# DIY-Cellphone.net
KiCad netlist of a schematic drawn in EAGLE
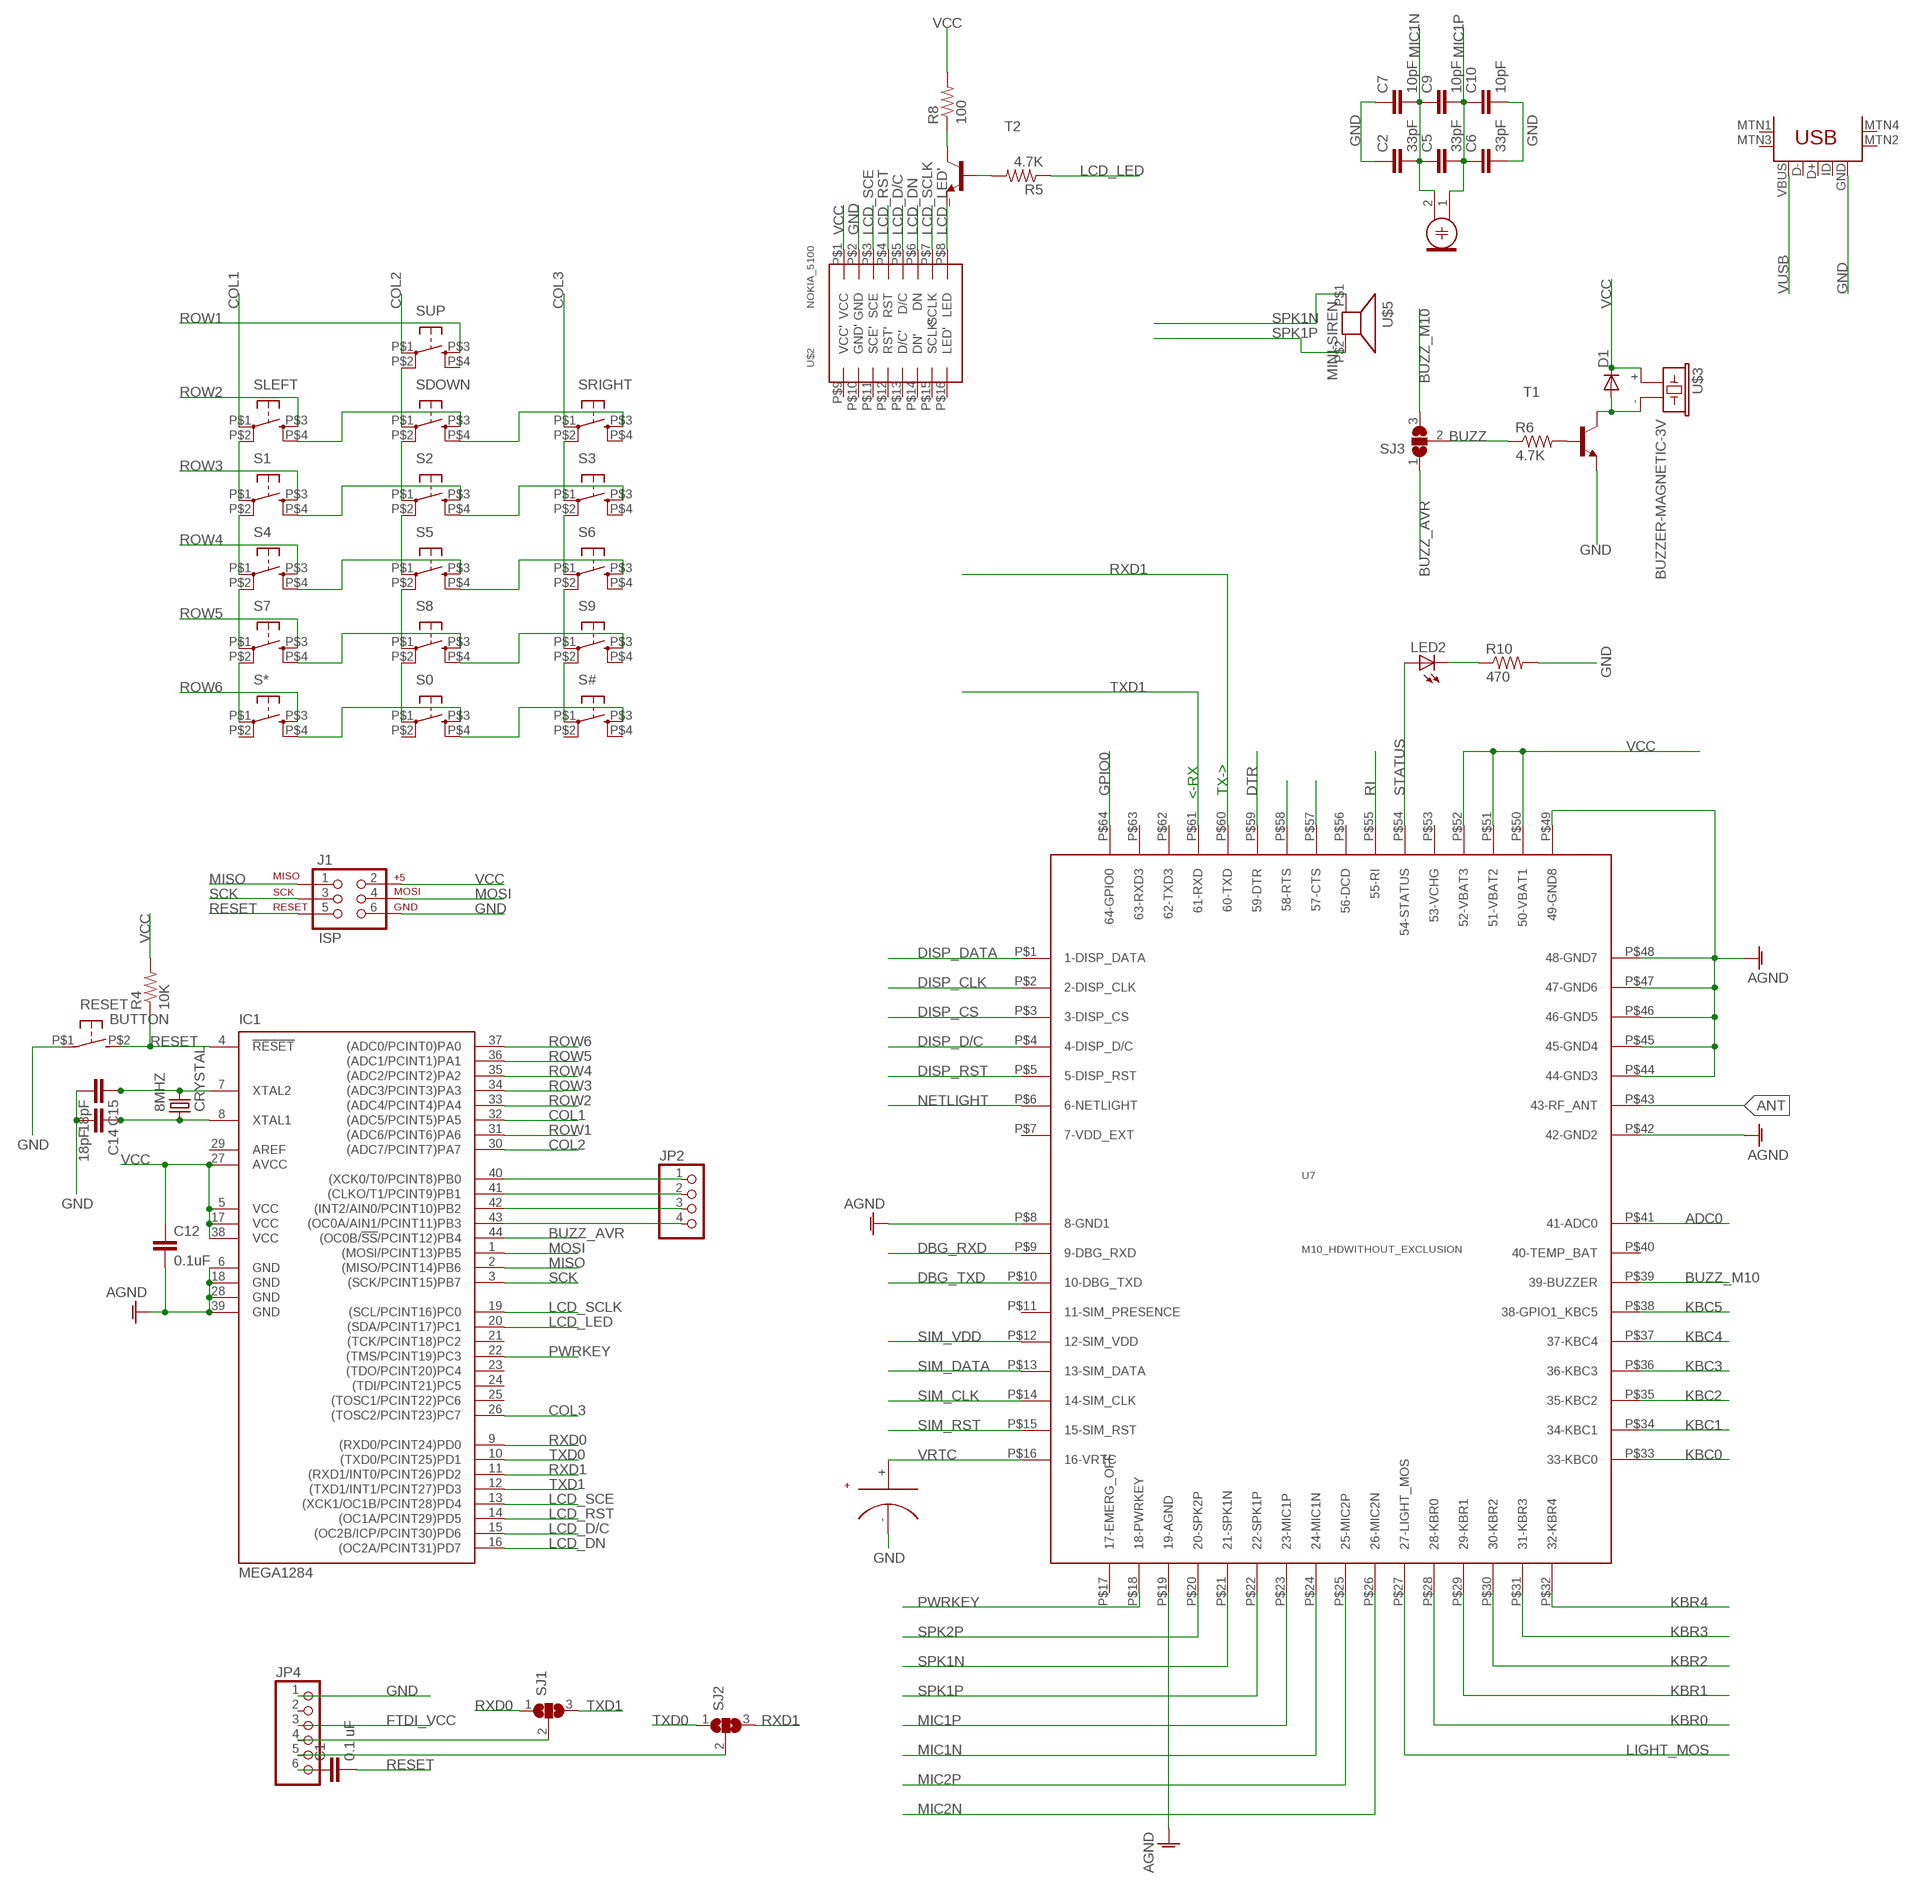
[diagram p0: schematic, sheet 1, part 1 of 2]
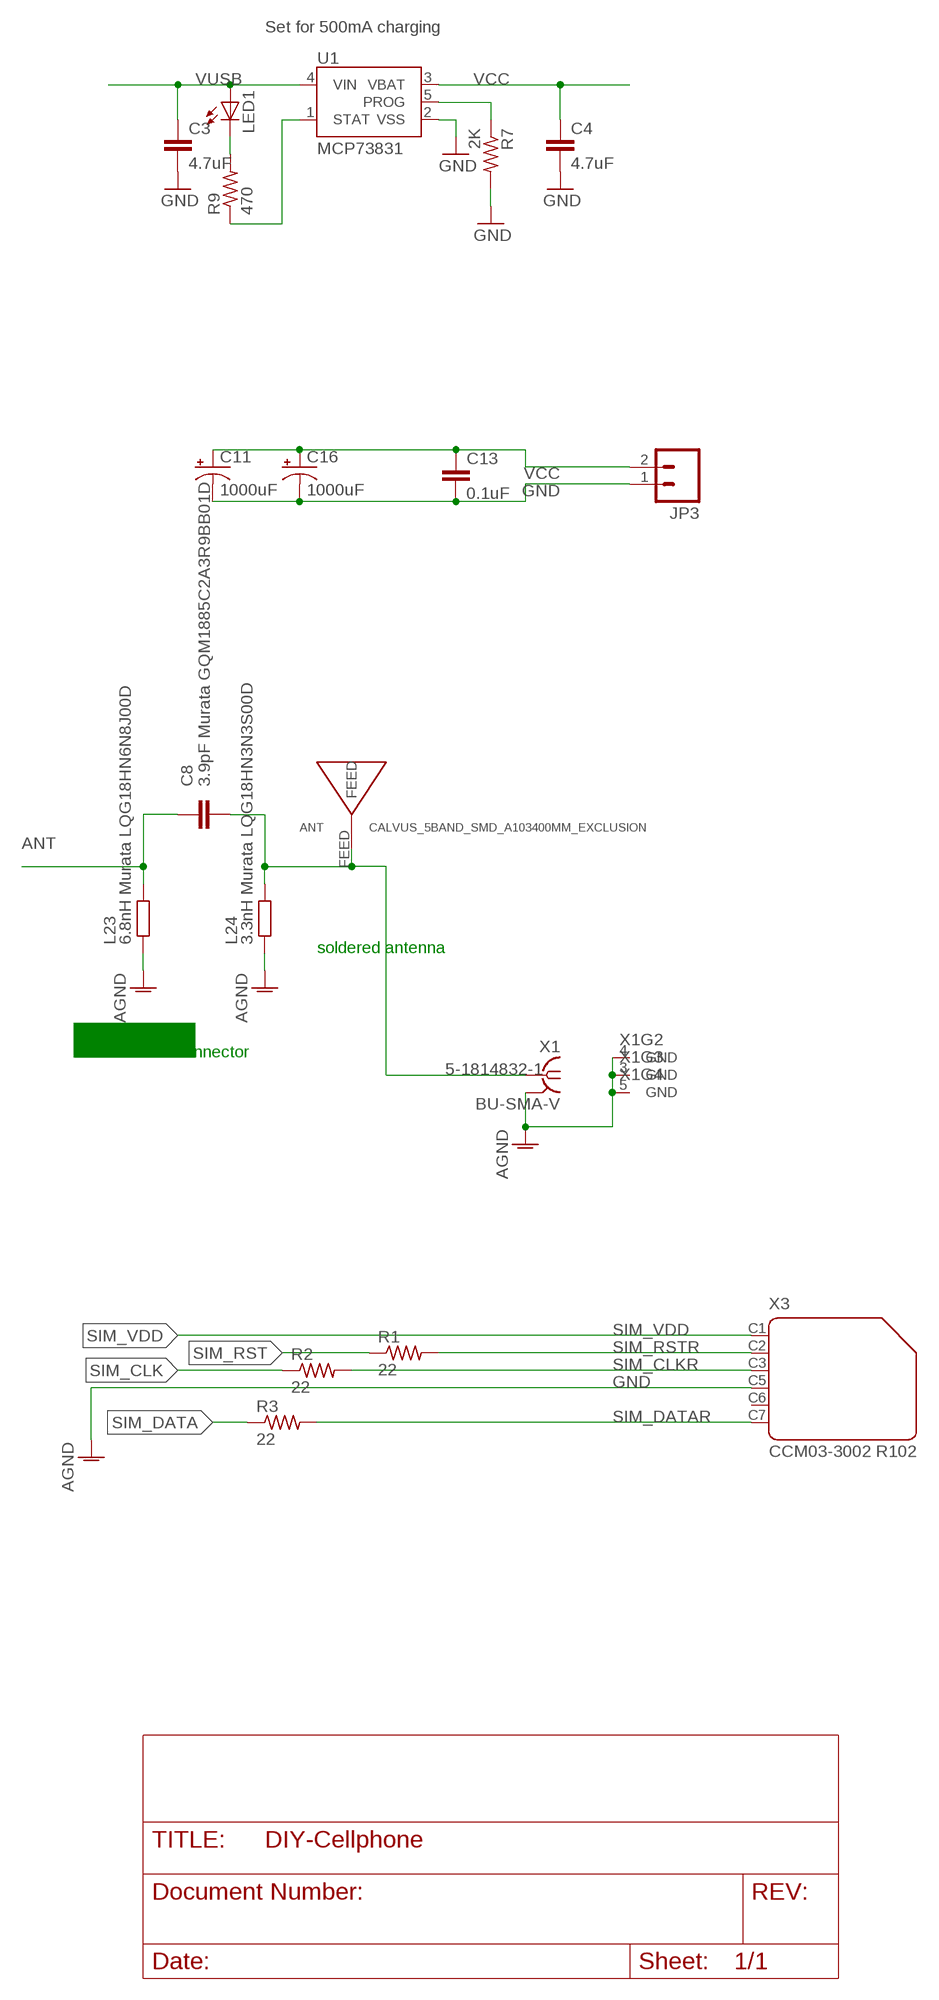
[diagram p1: schematic, sheet 1, part 2 of 2]

(export (version "E")
  (design (tool "Eeschema 10.0.6"))
  (components
    (comp (ref "8MHZ")
      (value "CRYSTAL")
      (footprint "eagle-import:2-SMD-5X3MM")
      (libsource (lib "eagle-import") (part "CRYSTAL"))
    )
    (comp (ref "ANT")
      (value "CALVUS_5BAND_SMD_A103400MM_EXCLUSION")
      (footprint "eagle-import:CALVUS_5BAND_SMD_A10340_0MM_EXCLUSION")
      (libsource (lib "eagle-import") (part "CALVUS_5BAND_SMD_A103400MM_EXCLUSION"))
    )
    (comp (ref "C1")
      (value "0.1 uF")
      (footprint "eagle-import:C1206")
      (libsource (lib "eagle-import") (part "cellphone-rcl_C-EUC1206"))
    )
    (comp (ref "C2")
      (value "33pF")
      (footprint "eagle-import:C1206")
      (libsource (lib "eagle-import") (part "cellphone-rcl_C-EUC1206"))
    )
    (comp (ref "C3")
      (value "4.7uF")
      (footprint "eagle-import:C1206")
      (libsource (lib "eagle-import") (part "cellphone-rcl_C-EUC1206"))
    )
    (comp (ref "C4")
      (value "4.7uF")
      (footprint "eagle-import:C1206")
      (libsource (lib "eagle-import") (part "cellphone-rcl_C-EUC1206"))
    )
    (comp (ref "C5")
      (value "33pF")
      (footprint "eagle-import:C1206")
      (libsource (lib "eagle-import") (part "cellphone-rcl_C-EUC1206"))
    )
    (comp (ref "C6")
      (value "33pF")
      (footprint "eagle-import:C1206")
      (libsource (lib "eagle-import") (part "cellphone-rcl_C-EUC1206"))
    )
    (comp (ref "C7")
      (value "10pF")
      (footprint "eagle-import:C1206")
      (libsource (lib "eagle-import") (part "cellphone-rcl_C-EUC1206"))
    )
    (comp (ref "C8")
      (value "3.9pF Murata GQM1885C2A3R9BB01D")
      (footprint "eagle-import:C0603-ROUND")
      (libsource (lib "eagle-import") (part "C-EU0603-RND"))
    )
    (comp (ref "C9")
      (value "10pF")
      (footprint "eagle-import:C1206")
      (libsource (lib "eagle-import") (part "cellphone-rcl_C-EUC1206"))
    )
    (comp (ref "C10")
      (value "10pF")
      (footprint "eagle-import:C1206")
      (libsource (lib "eagle-import") (part "cellphone-rcl_C-EUC1206"))
    )
    (comp (ref "C11")
      (value "1000uF")
      (footprint "eagle-import:D_7343-31R")
      (libsource (lib "eagle-import") (part "CPOL-USD/7343-31R"))
    )
    (comp (ref "C12")
      (value "0.1uF")
      (footprint "eagle-import:C1206")
      (libsource (lib "eagle-import") (part "cellphone-rcl_C-EUC1206"))
    )
    (comp (ref "C13")
      (value "0.1uF")
      (footprint "eagle-import:C1206")
      (libsource (lib "eagle-import") (part "cellphone-rcl_C-EUC1206"))
    )
    (comp (ref "C14")
      (value "18pF")
      (footprint "eagle-import:C1206")
      (libsource (lib "eagle-import") (part "cellphone-rcl_C-EUC1206"))
    )
    (comp (ref "C15")
      (value "18pF")
      (footprint "eagle-import:C1206")
      (libsource (lib "eagle-import") (part "cellphone-rcl_C-EUC1206"))
    )
    (comp (ref "C16")
      (value "1000uF")
      (footprint "eagle-import:D_7343-31R")
      (libsource (lib "eagle-import") (part "CPOL-USD/7343-31R"))
    )
    (comp (ref "D1")
      (value "DIODE-SOD123")
      (footprint "eagle-import:SOD123")
      (libsource (lib "eagle-import") (part "DIODE-SOD123"))
    )
    (comp (ref "IC1")
      (value "MEGA1284")
      (footprint "eagle-import:TQFP44")
      (libsource (lib "eagle-import") (part "MEGA164P/324P/644P-AU"))
    )
    (comp (ref "J1")
      (value "ISP")
      (footprint "eagle-import:2X3-NS")
      (libsource (lib "eagle-import") (part "AVR_SPI_PRG_6NS"))
    )
    (comp (ref "JP2")
      (value "PINHD-1X4")
      (footprint "eagle-import:1X04")
      (libsource (lib "eagle-import") (part "PINHD-1X4"))
    )
    (comp (ref "JP3")
      (value "M02-JST-2MM-SMT")
      (footprint "eagle-import:JST-2-SMD")
      (libsource (lib "eagle-import") (part "M02-JST-2MM-SMT"))
    )
    (comp (ref "JP4")
      (value "PINHD-1X6/90")
      (footprint "eagle-import:1X06_90")
      (libsource (lib "eagle-import") (part "PINHD-1X6/90"))
    )
    (comp (ref "L23")
      (value "6.8nH Murata LQG18HN6N8J00D")
      (footprint "eagle-import:R0603-ROUND")
      (libsource (lib "eagle-import") (part "R-EU_0603-RND"))
    )
    (comp (ref "L24")
      (value "3.3nH Murata LQG18HN3N3S00D")
      (footprint "eagle-import:R0603-ROUND")
      (libsource (lib "eagle-import") (part "R-EU_0603-RND"))
    )
    (comp (ref "LED1")
      (value "LEDSMT1206")
      (footprint "eagle-import:1206")
      (libsource (lib "eagle-import") (part "LEDSMT1206"))
    )
    (comp (ref "LED2")
      (value "LEDSMT1206")
      (footprint "eagle-import:1206")
      (libsource (lib "eagle-import") (part "LEDSMT1206"))
    )
    (comp (ref "MIC")
      (value "ELECTRET_MICROPHON-WM-64PC/64PK")
      (footprint "eagle-import:WM-64PC_64PK")
      (libsource (lib "eagle-import") (part "ELECTRET_MICROPHON-WM-64PC/64PK"))
    )
    (comp (ref "R1")
      (value "22")
      (footprint "eagle-import:R1206")
      (libsource (lib "eagle-import") (part "R-US_R1206"))
    )
    (comp (ref "R2")
      (value "22")
      (footprint "eagle-import:R1206")
      (libsource (lib "eagle-import") (part "R-US_R1206"))
    )
    (comp (ref "R3")
      (value "22")
      (footprint "eagle-import:R1206")
      (libsource (lib "eagle-import") (part "R-US_R1206"))
    )
    (comp (ref "R4")
      (value "10K")
      (footprint "eagle-import:R1206")
      (libsource (lib "eagle-import") (part "R-US_R1206"))
    )
    (comp (ref "R5")
      (value "4.7K")
      (footprint "eagle-import:R1206")
      (libsource (lib "eagle-import") (part "R-US_R1206"))
    )
    (comp (ref "R6")
      (value "4.7K")
      (footprint "eagle-import:R1206")
      (libsource (lib "eagle-import") (part "R-US_R1206"))
    )
    (comp (ref "R7")
      (value "2K")
      (footprint "eagle-import:R1206")
      (libsource (lib "eagle-import") (part "R-US_R1206"))
    )
    (comp (ref "R8")
      (value "100")
      (footprint "eagle-import:R1206")
      (libsource (lib "eagle-import") (part "R-US_R1206"))
    )
    (comp (ref "R9")
      (value "470")
      (footprint "eagle-import:R1206")
      (libsource (lib "eagle-import") (part "R-US_R1206"))
    )
    (comp (ref "R10")
      (value "470")
      (footprint "eagle-import:R1206")
      (libsource (lib "eagle-import") (part "R-US_R1206"))
    )
    (comp (ref "RESET")
      (value "BUTTON")
      (footprint "eagle-import:B3U-1000P")
      (libsource (lib "eagle-import") (part "BUTTON-2"))
    )
    (comp (ref "S#")
      (value "SWITCH-JLEAD")
      (footprint "eagle-import:BUTTON_6MM_JLEAD")
      (libsource (lib "eagle-import") (part "SWITCH-JLEAD"))
    )
    (comp (ref "S*")
      (value "SWITCH-JLEAD")
      (footprint "eagle-import:BUTTON_6MM_JLEAD")
      (libsource (lib "eagle-import") (part "SWITCH-JLEAD"))
    )
    (comp (ref "S0")
      (value "SWITCH-JLEAD")
      (footprint "eagle-import:BUTTON_6MM_JLEAD")
      (libsource (lib "eagle-import") (part "SWITCH-JLEAD"))
    )
    (comp (ref "S1")
      (value "SWITCH-JLEAD")
      (footprint "eagle-import:BUTTON_6MM_JLEAD")
      (libsource (lib "eagle-import") (part "SWITCH-JLEAD"))
    )
    (comp (ref "S2")
      (value "SWITCH-JLEAD")
      (footprint "eagle-import:BUTTON_6MM_JLEAD")
      (libsource (lib "eagle-import") (part "SWITCH-JLEAD"))
    )
    (comp (ref "S3")
      (value "SWITCH-JLEAD")
      (footprint "eagle-import:BUTTON_6MM_JLEAD")
      (libsource (lib "eagle-import") (part "SWITCH-JLEAD"))
    )
    (comp (ref "S4")
      (value "SWITCH-JLEAD")
      (footprint "eagle-import:BUTTON_6MM_JLEAD")
      (libsource (lib "eagle-import") (part "SWITCH-JLEAD"))
    )
    (comp (ref "S5")
      (value "SWITCH-JLEAD")
      (footprint "eagle-import:BUTTON_6MM_JLEAD")
      (libsource (lib "eagle-import") (part "SWITCH-JLEAD"))
    )
    (comp (ref "S6")
      (value "SWITCH-JLEAD")
      (footprint "eagle-import:BUTTON_6MM_JLEAD")
      (libsource (lib "eagle-import") (part "SWITCH-JLEAD"))
    )
    (comp (ref "S7")
      (value "SWITCH-JLEAD")
      (footprint "eagle-import:BUTTON_6MM_JLEAD")
      (libsource (lib "eagle-import") (part "SWITCH-JLEAD"))
    )
    (comp (ref "S8")
      (value "SWITCH-JLEAD")
      (footprint "eagle-import:BUTTON_6MM_JLEAD")
      (libsource (lib "eagle-import") (part "SWITCH-JLEAD"))
    )
    (comp (ref "S9")
      (value "SWITCH-JLEAD")
      (footprint "eagle-import:BUTTON_6MM_JLEAD")
      (libsource (lib "eagle-import") (part "SWITCH-JLEAD"))
    )
    (comp (ref "SDOWN")
      (value "SWITCH-JLEAD")
      (footprint "eagle-import:BUTTON_6MM_JLEAD")
      (libsource (lib "eagle-import") (part "SWITCH-JLEAD"))
    )
    (comp (ref "SJ1")
      (value "SJ2W")
      (footprint "eagle-import:SJ_2")
      (libsource (lib "eagle-import") (part "SJ2W"))
    )
    (comp (ref "SJ2")
      (value "SJ2W")
      (footprint "eagle-import:SJ_2")
      (libsource (lib "eagle-import") (part "SJ2W"))
    )
    (comp (ref "SJ3")
      (value "SJ2W")
      (footprint "eagle-import:SJ_2")
      (libsource (lib "eagle-import") (part "SJ2W"))
    )
    (comp (ref "SLEFT")
      (value "SWITCH-JLEAD")
      (footprint "eagle-import:BUTTON_6MM_JLEAD")
      (libsource (lib "eagle-import") (part "SWITCH-JLEAD"))
    )
    (comp (ref "SRIGHT")
      (value "SWITCH-JLEAD")
      (footprint "eagle-import:BUTTON_6MM_JLEAD")
      (libsource (lib "eagle-import") (part "SWITCH-JLEAD"))
    )
    (comp (ref "SUP")
      (value "SWITCH-JLEAD")
      (footprint "eagle-import:BUTTON_6MM_JLEAD")
      (libsource (lib "eagle-import") (part "SWITCH-JLEAD"))
    )
    (comp (ref "T1")
      (value "MMBT3904LT1-NPN-SOT23-BEC")
      (footprint "eagle-import:SOT23-BEC")
      (libsource (lib "eagle-import") (part "-NPN-SOT23-BECMMBT3904LT1"))
    )
    (comp (ref "T2")
      (value "MMBT3904LT1-NPN-SOT23-BEC")
      (footprint "eagle-import:SOT23-BEC")
      (libsource (lib "eagle-import") (part "-NPN-SOT23-BECMMBT3904LT1"))
    )
    (comp (ref "U$1")
      (value "USB-MINIB-5PIN")
      (footprint "eagle-import:USB-MINIB")
      (libsource (lib "eagle-import") (part "USB-MINIB-5PIN"))
    )
    (comp (ref "U$2")
      (value "NOKIA_5100")
      (footprint "eagle-import:NOKIA_5100_SPARKFUN")
      (libsource (lib "eagle-import") (part "NOKIA_5100"))
    )
    (comp (ref "U$3")
      (value "BUZZER-MAGNETIC-3V")
      (footprint "eagle-import:PUI-SMT-0540")
      (libsource (lib "eagle-import") (part "BUZZER-MAGNETIC-3V"))
    )
    (comp (ref "U$4")
      (value "SUPERCAPPAS")
      (footprint "eagle-import:414-VA5R")
      (libsource (lib "eagle-import") (part "SUPERCAPPAS"))
    )
    (comp (ref "U$5")
      (value "MINI-SIREN")
      (footprint "eagle-import:SPEAKER-6.4MM")
      (libsource (lib "eagle-import") (part "MINI-SIREN"))
    )
    (comp (ref "U1")
      (value "MCP73831")
      (footprint "eagle-import:SOT23-5")
      (libsource (lib "eagle-import") (part "MCP73831"))
    )
    (comp (ref "U7")
      (value "M10_HDWITHOUT_EXCLUSION")
      (footprint "eagle-import:M10_HD_WITHOUT_EXCLUSION")
      (libsource (lib "eagle-import") (part "M10_HDWITHOUT_EXCLUSION"))
    )
    (comp (ref "X1")
      (value "BU-SMA-V")
      (footprint "eagle-import:BU-SMA-V")
      (fields (field (name "PN") "5-1814832-1"))
      (libsource (lib "eagle-import") (part "BU-SMA-V"))
    )
    (comp (ref "X3")
      (value "CCM03-3002 R102")
      (footprint "eagle-import:CON-AMPHENOL_C707_10M006_512_2")
      (fields (field (name "OC_FARNELL") "1463072 "))
      (libsource (lib "eagle-import") (part "CON-AMPHENOL_SIMLOCK-C707_10M006_512_2"))
    )
  )
  (nets
    (net (code "1") (name "/ADC0") (class "Default")
      (node (ref "U7") (pin "P$41") (pinfunction "41-ADC0_P$41") (pintype "bidirectional"))
    )
    (net (code "2") (name "/AREF") (class "Default")
      (node (ref "IC1") (pin "29") (pinfunction "AREF_29") (pintype "power_in"))
    )
    (net (code "3") (name "/BUZZ") (class "Default")
      (node (ref "R6") (pin "1") (pinfunction "1_1") (pintype "passive"))
      (node (ref "SJ3") (pin "2") (pinfunction "2_2") (pintype "passive"))
    )
    (net (code "4") (name "/BUZZ_AVR") (class "Default")
      (node (ref "IC1") (pin "44") (pinfunction "(OC0B/~{SS}/PCINT12)PB4_44") (pintype "bidirectional"))
      (node (ref "SJ3") (pin "1") (pinfunction "1_1") (pintype "passive"))
    )
    (net (code "5") (name "/BUZZ_M10") (class "Default")
      (node (ref "SJ3") (pin "3") (pinfunction "3_3") (pintype "passive"))
      (node (ref "U7") (pin "P$39") (pinfunction "39-BUZZER_P$39") (pintype "bidirectional"))
    )
    (net (code "6") (name "/COL1") (class "Default")
      (node (ref "IC1") (pin "32") (pinfunction "(ADC5/PCINT5)PA5_32") (pintype "bidirectional"))
      (node (ref "SLEFT") (pin "P$1") (pinfunction "P_P$1") (pintype "passive"))
    )
    (net (code "7") (name "/COL2") (class "Default")
      (node (ref "IC1") (pin "30") (pinfunction "(ADC7/PCINT7)PA7_30") (pintype "bidirectional"))
      (node (ref "SUP") (pin "P$1") (pinfunction "P_P$1") (pintype "passive"))
    )
    (net (code "8") (name "/COL3") (class "Default")
      (node (ref "IC1") (pin "26") (pinfunction "(TOSC2/PCINT23)PC7_26") (pintype "bidirectional"))
      (node (ref "SRIGHT") (pin "P$1") (pinfunction "P_P$1") (pintype "passive"))
    )
    (net (code "9") (name "/DBG_RXD") (class "Default")
      (node (ref "U7") (pin "P$9") (pinfunction "9-DBG_RXD_P$9") (pintype "bidirectional"))
    )
    (net (code "10") (name "/DBG_TXD") (class "Default")
      (node (ref "U7") (pin "P$10") (pinfunction "10-DBG_TXD_P$10") (pintype "bidirectional"))
    )
    (net (code "11") (name "/DISP_CLK") (class "Default")
      (node (ref "U7") (pin "P$2") (pinfunction "2-DISP_CLK_P$2") (pintype "bidirectional"))
    )
    (net (code "12") (name "/DISP_CS") (class "Default")
      (node (ref "U7") (pin "P$3") (pinfunction "3-DISP_CS_P$3") (pintype "bidirectional"))
    )
    (net (code "13") (name "/DISP_DATA") (class "Default")
      (node (ref "U7") (pin "P$1") (pinfunction "1-DISP_DATA_P$1") (pintype "bidirectional"))
    )
    (net (code "14") (name "/DISP_D{slash}C") (class "Default")
      (node (ref "U7") (pin "P$4") (pinfunction "4-DISP_D/C_P$4") (pintype "bidirectional"))
    )
    (net (code "15") (name "/DISP_RST") (class "Default")
      (node (ref "U7") (pin "P$5") (pinfunction "5-DISP_RST_P$5") (pintype "bidirectional"))
    )
    (net (code "16") (name "/DTR") (class "Default")
      (node (ref "U7") (pin "P$59") (pinfunction "59-DTR_P$59") (pintype "bidirectional"))
    )
    (net (code "17") (name "/FTDI_VCC") (class "Default")
      (node (ref "JP4") (pin "3") (pinfunction "3_3") (pintype "passive"))
    )
    (net (code "18") (name "/GPIO0") (class "Default")
      (node (ref "U7") (pin "P$64") (pinfunction "64-GPIO0_P$64") (pintype "bidirectional"))
    )
    (net (code "19") (name "/KBC0") (class "Default")
      (node (ref "U7") (pin "P$33") (pinfunction "33-KBC0_P$33") (pintype "bidirectional"))
    )
    (net (code "20") (name "/KBC1") (class "Default")
      (node (ref "U7") (pin "P$34") (pinfunction "34-KBC1_P$34") (pintype "bidirectional"))
    )
    (net (code "21") (name "/KBC2") (class "Default")
      (node (ref "U7") (pin "P$35") (pinfunction "35-KBC2_P$35") (pintype "bidirectional"))
    )
    (net (code "22") (name "/KBC3") (class "Default")
      (node (ref "U7") (pin "P$36") (pinfunction "36-KBC3_P$36") (pintype "bidirectional"))
    )
    (net (code "23") (name "/KBC4") (class "Default")
      (node (ref "U7") (pin "P$37") (pinfunction "37-KBC4_P$37") (pintype "bidirectional"))
    )
    (net (code "24") (name "/KBC5") (class "Default")
      (node (ref "U7") (pin "P$38") (pinfunction "38-GPIO1_KBC5_P$38") (pintype "bidirectional"))
    )
    (net (code "25") (name "/KBR0") (class "Default")
      (node (ref "U7") (pin "P$28") (pinfunction "28-KBR0_P$28") (pintype "bidirectional"))
    )
    (net (code "26") (name "/KBR1") (class "Default")
      (node (ref "U7") (pin "P$29") (pinfunction "29-KBR1_P$29") (pintype "bidirectional"))
    )
    (net (code "27") (name "/KBR2") (class "Default")
      (node (ref "U7") (pin "P$30") (pinfunction "30-KBR2_P$30") (pintype "bidirectional"))
    )
    (net (code "28") (name "/KBR3") (class "Default")
      (node (ref "U7") (pin "P$31") (pinfunction "31-KBR3_P$31") (pintype "bidirectional"))
    )
    (net (code "29") (name "/KBR4") (class "Default")
      (node (ref "U7") (pin "P$32") (pinfunction "32-KBR4_P$32") (pintype "bidirectional"))
    )
    (net (code "30") (name "/LCD_DN") (class "Default")
      (node (ref "IC1") (pin "16") (pinfunction "(OC2A/PCINT31)PD7_16") (pintype "bidirectional"))
      (node (ref "U$2") (pin "P$6") (pinfunction "DN_P$6") (pintype "bidirectional"))
    )
    (net (code "31") (name "/LCD_D{slash}C") (class "Default")
      (node (ref "IC1") (pin "15") (pinfunction "(OC2B/ICP/PCINT30)PD6_15") (pintype "bidirectional"))
      (node (ref "U$2") (pin "P$5") (pinfunction "D/C_P$5") (pintype "bidirectional"))
    )
    (net (code "32") (name "/LCD_LED") (class "Default")
      (node (ref "IC1") (pin "20") (pinfunction "(SDA/PCINT17)PC1_20") (pintype "bidirectional"))
      (node (ref "R5") (pin "1") (pinfunction "1_1") (pintype "passive"))
    )
    (net (code "33") (name "/LCD_LED'") (class "Default")
      (node (ref "T2") (pin "E") (pinfunction "E_E") (pintype "passive"))
      (node (ref "U$2") (pin "P$8") (pinfunction "LED_P$8") (pintype "bidirectional"))
    )
    (net (code "34") (name "/LCD_RST") (class "Default")
      (node (ref "IC1") (pin "14") (pinfunction "(OC1A/PCINT29)PD5_14") (pintype "bidirectional"))
      (node (ref "U$2") (pin "P$4") (pinfunction "RST_P$4") (pintype "bidirectional"))
    )
    (net (code "35") (name "/LCD_SCE") (class "Default")
      (node (ref "IC1") (pin "13") (pinfunction "(XCK1/OC1B/PCINT28)PD4_13") (pintype "bidirectional"))
      (node (ref "U$2") (pin "P$3") (pinfunction "SCE_P$3") (pintype "bidirectional"))
    )
    (net (code "36") (name "/LCD_SCLK") (class "Default")
      (node (ref "IC1") (pin "19") (pinfunction "(SCL/PCINT16)PC0_19") (pintype "bidirectional"))
      (node (ref "U$2") (pin "P$7") (pinfunction "SCLK_P$7") (pintype "bidirectional"))
    )
    (net (code "37") (name "/LIGHT_MOS") (class "Default")
      (node (ref "U7") (pin "P$27") (pinfunction "27-LIGHT_MOS_P$27") (pintype "bidirectional"))
    )
    (net (code "38") (name "/MIC1N") (class "Default")
      (node (ref "C2") (pin "2") (pinfunction "2_2") (pintype "passive"))
      (node (ref "C5") (pin "1") (pinfunction "1_1") (pintype "passive"))
      (node (ref "C7") (pin "2") (pinfunction "2_2") (pintype "passive"))
      (node (ref "C9") (pin "1") (pinfunction "1_1") (pintype "passive"))
      (node (ref "MIC") (pin "2") (pinfunction "2_2") (pintype "passive"))
      (node (ref "U7") (pin "P$24") (pinfunction "24-MIC1N_P$24") (pintype "bidirectional"))
    )
    (net (code "39") (name "/MIC1P") (class "Default")
      (node (ref "C10") (pin "1") (pinfunction "1_1") (pintype "passive"))
      (node (ref "C5") (pin "2") (pinfunction "2_2") (pintype "passive"))
      (node (ref "C6") (pin "1") (pinfunction "1_1") (pintype "passive"))
      (node (ref "C9") (pin "2") (pinfunction "2_2") (pintype "passive"))
      (node (ref "MIC") (pin "1") (pinfunction "1_1") (pintype "passive"))
      (node (ref "U7") (pin "P$23") (pinfunction "23-MIC1P_P$23") (pintype "bidirectional"))
    )
    (net (code "40") (name "/MIC2N") (class "Default")
      (node (ref "U7") (pin "P$26") (pinfunction "26-MIC2N_P$26") (pintype "bidirectional"))
    )
    (net (code "41") (name "/MIC2P") (class "Default")
      (node (ref "U7") (pin "P$25") (pinfunction "25-MIC2P_P$25") (pintype "bidirectional"))
    )
    (net (code "42") (name "/MISO") (class "Default")
      (node (ref "IC1") (pin "2") (pinfunction "(MISO/PCINT14)PB6_2") (pintype "bidirectional"))
      (node (ref "J1") (pin "1") (pinfunction "1_1") (pintype "passive"))
    )
    (net (code "43") (name "/MOSI") (class "Default")
      (node (ref "IC1") (pin "1") (pinfunction "(MOSI/PCINT13)PB5_1") (pintype "bidirectional"))
      (node (ref "J1") (pin "4") (pinfunction "4_4") (pintype "passive"))
    )
    (net (code "44") (name "/NETLIGHT") (class "Default")
      (node (ref "U7") (pin "P$6") (pinfunction "6-NETLIGHT_P$6") (pintype "bidirectional"))
    )
    (net (code "45") (name "/PWRKEY") (class "Default")
      (node (ref "IC1") (pin "22") (pinfunction "(TMS/PCINT19)PC3_22") (pintype "bidirectional"))
      (node (ref "U7") (pin "P$18") (pinfunction "18-PWRKEY_P$18") (pintype "bidirectional"))
    )
    (net (code "46") (name "/RESET") (class "Default")
      (node (ref "C1") (pin "2") (pinfunction "2_2") (pintype "passive"))
      (node (ref "IC1") (pin "4") (pinfunction "~{RESET}_4") (pintype "input"))
      (node (ref "J1") (pin "5") (pinfunction "5_5") (pintype "passive"))
      (node (ref "R4") (pin "1") (pinfunction "1_1") (pintype "passive"))
      (node (ref "RESET") (pin "P$2") (pinfunction "S_P$2") (pintype "passive"))
    )
    (net (code "47") (name "/RI") (class "Default")
      (node (ref "U7") (pin "P$55") (pinfunction "55-RI_P$55") (pintype "bidirectional"))
    )
    (net (code "48") (name "/ROW1") (class "Default")
      (node (ref "IC1") (pin "31") (pinfunction "(ADC6/PCINT6)PA6_31") (pintype "bidirectional"))
      (node (ref "SUP") (pin "P$3") (pinfunction "S_P$3") (pintype "passive"))
    )
    (net (code "49") (name "/ROW2") (class "Default")
      (node (ref "IC1") (pin "33") (pinfunction "(ADC4/PCINT4)PA4_33") (pintype "bidirectional"))
      (node (ref "SLEFT") (pin "P$3") (pinfunction "S_P$3") (pintype "passive"))
    )
    (net (code "50") (name "/ROW3") (class "Default")
      (node (ref "IC1") (pin "34") (pinfunction "(ADC3/PCINT3)PA3_34") (pintype "bidirectional"))
      (node (ref "S1") (pin "P$3") (pinfunction "S_P$3") (pintype "passive"))
    )
    (net (code "51") (name "/ROW4") (class "Default")
      (node (ref "IC1") (pin "35") (pinfunction "(ADC2/PCINT2)PA2_35") (pintype "bidirectional"))
      (node (ref "S4") (pin "P$3") (pinfunction "S_P$3") (pintype "passive"))
    )
    (net (code "52") (name "/ROW5") (class "Default")
      (node (ref "IC1") (pin "36") (pinfunction "(ADC1/PCINT1)PA1_36") (pintype "bidirectional"))
      (node (ref "S7") (pin "P$3") (pinfunction "S_P$3") (pintype "passive"))
    )
    (net (code "53") (name "/ROW6") (class "Default")
      (node (ref "IC1") (pin "37") (pinfunction "(ADC0/PCINT0)PA0_37") (pintype "bidirectional"))
      (node (ref "S*") (pin "P$3") (pinfunction "S_P$3") (pintype "passive"))
    )
    (net (code "54") (name "/RXD0") (class "Default")
      (node (ref "IC1") (pin "9") (pinfunction "(RXD0/PCINT24)PD0_9") (pintype "bidirectional"))
      (node (ref "SJ1") (pin "1") (pinfunction "1_1") (pintype "passive"))
    )
    (net (code "55") (name "/RXD1") (class "Default")
      (node (ref "IC1") (pin "11") (pinfunction "(RXD1/INT0/PCINT26)PD2_11") (pintype "bidirectional"))
      (node (ref "SJ2") (pin "3") (pinfunction "3_3") (pintype "passive"))
      (node (ref "U7") (pin "P$60") (pinfunction "60-TXD_P$60") (pintype "bidirectional"))
    )
    (net (code "56") (name "/SCK") (class "Default")
      (node (ref "IC1") (pin "3") (pinfunction "(SCK/PCINT15)PB7_3") (pintype "bidirectional"))
      (node (ref "J1") (pin "3") (pinfunction "3_3") (pintype "passive"))
    )
    (net (code "57") (name "/SIM_CLKR") (class "Default")
      (node (ref "R2") (pin "2") (pinfunction "2_2") (pintype "passive"))
      (node (ref "X3") (pin "C3") (pinfunction "3_C3") (pintype "passive"))
    )
    (net (code "58") (name "/SIM_DATAR") (class "Default")
      (node (ref "R3") (pin "2") (pinfunction "2_2") (pintype "passive"))
      (node (ref "X3") (pin "C7") (pinfunction "6_C7") (pintype "passive"))
    )
    (net (code "59") (name "/SIM_RSTR") (class "Default")
      (node (ref "R1") (pin "2") (pinfunction "2_2") (pintype "passive"))
      (node (ref "X3") (pin "C2") (pinfunction "2_C2") (pintype "passive"))
    )
    (net (code "60") (name "/SPK1N") (class "Default")
      (node (ref "U$5") (pin "P$1") (pinfunction "1_P$1") (pintype "passive"))
      (node (ref "U7") (pin "P$21") (pinfunction "21-SPK1N_P$21") (pintype "bidirectional"))
    )
    (net (code "61") (name "/SPK1P") (class "Default")
      (node (ref "U$5") (pin "P$2") (pinfunction "2_P$2") (pintype "passive"))
      (node (ref "U7") (pin "P$22") (pinfunction "22-SPK1P_P$22") (pintype "bidirectional"))
    )
    (net (code "62") (name "/SPK2P") (class "Default")
      (node (ref "U7") (pin "P$20") (pinfunction "20-SPK2P_P$20") (pintype "bidirectional"))
    )
    (net (code "63") (name "/STATUS") (class "Default")
      (node (ref "LED2") (pin "A") (pinfunction "A_A") (pintype "passive"))
      (node (ref "U7") (pin "P$54") (pinfunction "54-STATUS_P$54") (pintype "bidirectional"))
    )
    (net (code "64") (name "/TXD0") (class "Default")
      (node (ref "IC1") (pin "10") (pinfunction "(TXD0/PCINT25)PD1_10") (pintype "bidirectional"))
      (node (ref "SJ2") (pin "1") (pinfunction "1_1") (pintype "passive"))
    )
    (net (code "65") (name "/TXD1") (class "Default")
      (node (ref "IC1") (pin "12") (pinfunction "(TXD1/INT1/PCINT27)PD3_12") (pintype "bidirectional"))
      (node (ref "SJ1") (pin "3") (pinfunction "3_3") (pintype "passive"))
      (node (ref "U7") (pin "P$61") (pinfunction "61-RXD_P$61") (pintype "bidirectional"))
    )
    (net (code "66") (name "/VCC") (class "Default")
      (node (ref "C11") (pin "+") (pinfunction "+_+") (pintype "passive"))
      (node (ref "C12") (pin "1") (pinfunction "1_1") (pintype "passive"))
      (node (ref "C13") (pin "1") (pinfunction "1_1") (pintype "passive"))
      (node (ref "C16") (pin "+") (pinfunction "+_+") (pintype "passive"))
      (node (ref "C4") (pin "1") (pinfunction "1_1") (pintype "passive"))
      (node (ref "D1") (pin "C") (pinfunction "C_C") (pintype "passive"))
      (node (ref "IC1") (pin "17") (pinfunction "VCC_17") (pintype "power_in"))
      (node (ref "IC1") (pin "27") (pinfunction "AVCC_27") (pintype "power_in"))
      (node (ref "IC1") (pin "38") (pinfunction "VCC_38") (pintype "power_in"))
      (node (ref "IC1") (pin "5") (pinfunction "VCC_5") (pintype "power_in"))
      (node (ref "J1") (pin "2") (pinfunction "2_2") (pintype "passive"))
      (node (ref "JP3") (pin "2") (pinfunction "1_2") (pintype "passive"))
      (node (ref "R4") (pin "2") (pinfunction "2_2") (pintype "passive"))
      (node (ref "R8") (pin "2") (pinfunction "2_2") (pintype "passive"))
      (node (ref "U$2") (pin "P$1") (pinfunction "VCC_P$1") (pintype "bidirectional"))
      (node (ref "U$3") (pin "+") (pinfunction "1_+") (pintype "passive"))
      (node (ref "U1") (pin "3") (pinfunction "VBAT_3") (pintype "power_in"))
      (node (ref "U7") (pin "P$50") (pinfunction "50-VBAT1_P$50") (pintype "bidirectional"))
      (node (ref "U7") (pin "P$51") (pinfunction "51-VBAT2_P$51") (pintype "bidirectional"))
      (node (ref "U7") (pin "P$52") (pinfunction "52-VBAT3_P$52") (pintype "bidirectional"))
    )
    (net (code "67") (name "/VRTC") (class "Default")
      (node (ref "U$4") (pin "+") (pinfunction "+_+") (pintype "bidirectional"))
      (node (ref "U7") (pin "P$16") (pinfunction "16-VRTC_P$16") (pintype "bidirectional"))
    )
    (net (code "68") (name "/VUSB") (class "Default")
      (node (ref "C3") (pin "1") (pinfunction "1_1") (pintype "passive"))
      (node (ref "LED1") (pin "A") (pinfunction "A_A") (pintype "passive"))
      (node (ref "U$1") (pin "VBUS") (pinfunction "VBUS_VBUS") (pintype "bidirectional"))
      (node (ref "U1") (pin "4") (pinfunction "VIN_4") (pintype "power_in"))
    )
    (net (code "69") (name "AGND") (class "Default")
      (node (ref "C10") (pin "2") (pinfunction "2_2") (pintype "passive"))
      (node (ref "C11") (pin "-") (pinfunction "-_-") (pintype "passive"))
      (node (ref "C12") (pin "2") (pinfunction "2_2") (pintype "passive"))
      (node (ref "C13") (pin "2") (pinfunction "2_2") (pintype "passive"))
      (node (ref "C14") (pin "2") (pinfunction "2_2") (pintype "passive"))
      (node (ref "C15") (pin "2") (pinfunction "2_2") (pintype "passive"))
      (node (ref "C16") (pin "-") (pinfunction "-_-") (pintype "passive"))
      (node (ref "C2") (pin "1") (pinfunction "1_1") (pintype "passive"))
      (node (ref "C3") (pin "2") (pinfunction "2_2") (pintype "passive"))
      (node (ref "C4") (pin "2") (pinfunction "2_2") (pintype "passive"))
      (node (ref "C6") (pin "2") (pinfunction "2_2") (pintype "passive"))
      (node (ref "C7") (pin "1") (pinfunction "1_1") (pintype "passive"))
      (node (ref "IC1") (pin "18") (pinfunction "GND_18") (pintype "power_in"))
      (node (ref "IC1") (pin "28") (pinfunction "GND_28") (pintype "power_in"))
      (node (ref "IC1") (pin "39") (pinfunction "GND_39") (pintype "power_in"))
      (node (ref "IC1") (pin "6") (pinfunction "GND_6") (pintype "power_in"))
      (node (ref "J1") (pin "6") (pinfunction "6_6") (pintype "passive"))
      (node (ref "JP3") (pin "1") (pinfunction "2_1") (pintype "passive"))
      (node (ref "JP4") (pin "1") (pinfunction "1_1") (pintype "passive"))
      (node (ref "L23") (pin "1") (pinfunction "1_1") (pintype "passive"))
      (node (ref "L24") (pin "1") (pinfunction "1_1") (pintype "passive"))
      (node (ref "R10") (pin "2") (pinfunction "2_2") (pintype "passive"))
      (node (ref "R7") (pin "2") (pinfunction "2_2") (pintype "passive"))
      (node (ref "RESET") (pin "P$1") (pinfunction "P_P$1") (pintype "passive"))
      (node (ref "T1") (pin "E") (pinfunction "E_E") (pintype "passive"))
      (node (ref "U$1") (pin "GND") (pinfunction "GND_GND") (pintype "bidirectional"))
      (node (ref "U$2") (pin "P$2") (pinfunction "GND_P$2") (pintype "bidirectional"))
      (node (ref "U$4") (pin "-") (pinfunction "-_-") (pintype "bidirectional"))
      (node (ref "U1") (pin "2") (pinfunction "VSS_2") (pintype "power_in"))
      (node (ref "U7") (pin "P$19") (pinfunction "19-AGND_P$19") (pintype "bidirectional"))
      (node (ref "U7") (pin "P$42") (pinfunction "42-GND2_P$42") (pintype "bidirectional"))
      (node (ref "U7") (pin "P$44") (pinfunction "44-GND3_P$44") (pintype "bidirectional"))
      (node (ref "U7") (pin "P$45") (pinfunction "45-GND4_P$45") (pintype "bidirectional"))
      (node (ref "U7") (pin "P$46") (pinfunction "46-GND5_P$46") (pintype "bidirectional"))
      (node (ref "U7") (pin "P$47") (pinfunction "47-GND6_P$47") (pintype "bidirectional"))
      (node (ref "U7") (pin "P$48") (pinfunction "48-GND7_P$48") (pintype "bidirectional"))
      (node (ref "U7") (pin "P$49") (pinfunction "49-GND8_P$49") (pintype "bidirectional"))
      (node (ref "U7") (pin "P$8") (pinfunction "8-GND1_P$8") (pintype "bidirectional"))
      (node (ref "X1") (pin "2") (pinfunction "GND_2") (pintype "power_in"))
      (node (ref "X1") (pin "3") (pinfunction "GND_3") (pintype "power_in"))
      (node (ref "X1") (pin "4") (pinfunction "GND_4") (pintype "power_in"))
      (node (ref "X1") (pin "5") (pinfunction "GND_5") (pintype "power_in"))
      (node (ref "X3") (pin "C5") (pinfunction "4_C5") (pintype "passive"))
    )
    (net (code "70") (name "ANT") (class "Default")
      (node (ref "C8") (pin "1") (pinfunction "1_1") (pintype "passive"))
      (node (ref "L23") (pin "2") (pinfunction "2_2") (pintype "passive"))
      (node (ref "U7") (pin "P$43") (pinfunction "43-RF_ANT_P$43") (pintype "bidirectional"))
    )
    (net (code "71") (name "Net-(8MHZ-1)") (class "Default")
      (node (ref "8MHZ") (pin "P$1") (pinfunction "1_P$1") (pintype "passive"))
      (node (ref "C14") (pin "1") (pinfunction "1_1") (pintype "passive"))
      (node (ref "IC1") (pin "8") (pinfunction "XTAL1_8") (pintype "input"))
    )
    (net (code "72") (name "Net-(8MHZ-2)") (class "Default")
      (node (ref "8MHZ") (pin "P$2") (pinfunction "2_P$2") (pintype "passive"))
      (node (ref "C15") (pin "1") (pinfunction "1_1") (pintype "passive"))
      (node (ref "IC1") (pin "7") (pinfunction "XTAL2_7") (pintype "output"))
    )
    (net (code "73") (name "Net-(ANT-PadFEED)") (class "Default")
      (node (ref "ANT") (pin "FEED") (pinfunction "FEED_FEED") (pintype "bidirectional"))
      (node (ref "C8") (pin "2") (pinfunction "2_2") (pintype "passive"))
      (node (ref "L24") (pin "2") (pinfunction "2_2") (pintype "passive"))
      (node (ref "X1") (pin "1") (pinfunction "1_1") (pintype "passive"))
    )
    (net (code "74") (name "Net-(C1-Pad1)") (class "Default")
      (node (ref "C1") (pin "1") (pinfunction "1_1") (pintype "passive"))
      (node (ref "JP4") (pin "6") (pinfunction "6_6") (pintype "passive"))
    )
    (net (code "75") (name "Net-(IC1-(CLKO{slash}T1{slash}PCINT9)PB1)") (class "Default")
      (node (ref "IC1") (pin "41") (pinfunction "(CLKO/T1/PCINT9)PB1_41") (pintype "bidirectional"))
      (node (ref "JP2") (pin "2") (pinfunction "2_2") (pintype "passive"))
    )
    (net (code "76") (name "Net-(IC1-(INT2{slash}AIN0{slash}PCINT10)PB2)") (class "Default")
      (node (ref "IC1") (pin "42") (pinfunction "(INT2/AIN0/PCINT10)PB2_42") (pintype "bidirectional"))
      (node (ref "JP2") (pin "3") (pinfunction "3_3") (pintype "passive"))
    )
    (net (code "77") (name "Net-(IC1-(OC0A{slash}AIN1{slash}PCINT11)PB3)") (class "Default")
      (node (ref "IC1") (pin "43") (pinfunction "(OC0A/AIN1/PCINT11)PB3_43") (pintype "bidirectional"))
      (node (ref "JP2") (pin "4") (pinfunction "4_4") (pintype "passive"))
    )
    (net (code "78") (name "Net-(IC1-(XCK0{slash}T0{slash}PCINT8)PB0)") (class "Default")
      (node (ref "IC1") (pin "40") (pinfunction "(XCK0/T0/PCINT8)PB0_40") (pintype "bidirectional"))
      (node (ref "JP2") (pin "1") (pinfunction "1_1") (pintype "passive"))
    )
    (net (code "79") (name "Net-(JP4-Pad4)") (class "Default")
      (node (ref "JP4") (pin "4") (pinfunction "4_4") (pintype "passive"))
      (node (ref "SJ1") (pin "2") (pinfunction "2_2") (pintype "passive"))
    )
    (net (code "80") (name "Net-(JP4-Pad5)") (class "Default")
      (node (ref "JP4") (pin "5") (pinfunction "5_5") (pintype "passive"))
      (node (ref "SJ2") (pin "2") (pinfunction "2_2") (pintype "passive"))
    )
    (net (code "81") (name "Net-(LED1-PadC)") (class "Default")
      (node (ref "LED1") (pin "C") (pinfunction "C_C") (pintype "passive"))
      (node (ref "R9") (pin "2") (pinfunction "2_2") (pintype "passive"))
    )
    (net (code "82") (name "Net-(LED2-PadC)") (class "Default")
      (node (ref "LED2") (pin "C") (pinfunction "C_C") (pintype "passive"))
      (node (ref "R10") (pin "1") (pinfunction "1_1") (pintype "passive"))
    )
    (net (code "83") (name "Net-(R5-Pad2)") (class "Default")
      (node (ref "R5") (pin "2") (pinfunction "2_2") (pintype "passive"))
      (node (ref "T2") (pin "B") (pinfunction "B_B") (pintype "passive"))
    )
    (net (code "84") (name "Net-(R6-Pad2)") (class "Default")
      (node (ref "R6") (pin "2") (pinfunction "2_2") (pintype "passive"))
      (node (ref "T1") (pin "B") (pinfunction "B_B") (pintype "passive"))
    )
    (net (code "85") (name "Net-(R8-Pad1)") (class "Default")
      (node (ref "R8") (pin "1") (pinfunction "1_1") (pintype "passive"))
      (node (ref "T2") (pin "C") (pinfunction "C_C") (pintype "passive"))
    )
    (net (code "86") (name "Net-(S#-P)") (class "Default")
      (node (ref "S#") (pin "P$1") (pinfunction "P_P$1") (pintype "passive"))
      (node (ref "S9") (pin "P$2") (pinfunction "P1_P$2") (pintype "passive"))
    )
    (net (code "87") (name "Net-(S#-S)") (class "Default")
      (node (ref "S#") (pin "P$3") (pinfunction "S_P$3") (pintype "passive"))
      (node (ref "S0") (pin "P$4") (pinfunction "S1_P$4") (pintype "passive"))
    )
    (net (code "88") (name "Net-(S*-P)") (class "Default")
      (node (ref "S*") (pin "P$1") (pinfunction "P_P$1") (pintype "passive"))
      (node (ref "S7") (pin "P$2") (pinfunction "P1_P$2") (pintype "passive"))
    )
    (net (code "89") (name "Net-(S*-S1)") (class "Default")
      (node (ref "S*") (pin "P$4") (pinfunction "S1_P$4") (pintype "passive"))
      (node (ref "S0") (pin "P$3") (pinfunction "S_P$3") (pintype "passive"))
    )
    (net (code "90") (name "Net-(S0-P)") (class "Default")
      (node (ref "S0") (pin "P$1") (pinfunction "P_P$1") (pintype "passive"))
      (node (ref "S8") (pin "P$2") (pinfunction "P1_P$2") (pintype "passive"))
    )
    (net (code "91") (name "Net-(S1-P)") (class "Default")
      (node (ref "S1") (pin "P$1") (pinfunction "P_P$1") (pintype "passive"))
      (node (ref "SLEFT") (pin "P$2") (pinfunction "P1_P$2") (pintype "passive"))
    )
    (net (code "92") (name "Net-(S1-P1)") (class "Default")
      (node (ref "S1") (pin "P$2") (pinfunction "P1_P$2") (pintype "passive"))
      (node (ref "S4") (pin "P$1") (pinfunction "P_P$1") (pintype "passive"))
    )
    (net (code "93") (name "Net-(S1-S1)") (class "Default")
      (node (ref "S1") (pin "P$4") (pinfunction "S1_P$4") (pintype "passive"))
      (node (ref "S2") (pin "P$3") (pinfunction "S_P$3") (pintype "passive"))
    )
    (net (code "94") (name "Net-(S2-P)") (class "Default")
      (node (ref "S2") (pin "P$1") (pinfunction "P_P$1") (pintype "passive"))
      (node (ref "SDOWN") (pin "P$2") (pinfunction "P1_P$2") (pintype "passive"))
    )
    (net (code "95") (name "Net-(S2-P1)") (class "Default")
      (node (ref "S2") (pin "P$2") (pinfunction "P1_P$2") (pintype "passive"))
      (node (ref "S5") (pin "P$1") (pinfunction "P_P$1") (pintype "passive"))
    )
    (net (code "96") (name "Net-(S2-S1)") (class "Default")
      (node (ref "S2") (pin "P$4") (pinfunction "S1_P$4") (pintype "passive"))
      (node (ref "S3") (pin "P$3") (pinfunction "S_P$3") (pintype "passive"))
    )
    (net (code "97") (name "Net-(S3-P)") (class "Default")
      (node (ref "S3") (pin "P$1") (pinfunction "P_P$1") (pintype "passive"))
      (node (ref "SRIGHT") (pin "P$2") (pinfunction "P1_P$2") (pintype "passive"))
    )
    (net (code "98") (name "Net-(S3-P1)") (class "Default")
      (node (ref "S3") (pin "P$2") (pinfunction "P1_P$2") (pintype "passive"))
      (node (ref "S6") (pin "P$1") (pinfunction "P_P$1") (pintype "passive"))
    )
    (net (code "99") (name "Net-(S4-P1)") (class "Default")
      (node (ref "S4") (pin "P$2") (pinfunction "P1_P$2") (pintype "passive"))
      (node (ref "S7") (pin "P$1") (pinfunction "P_P$1") (pintype "passive"))
    )
    (net (code "100") (name "Net-(S4-S1)") (class "Default")
      (node (ref "S4") (pin "P$4") (pinfunction "S1_P$4") (pintype "passive"))
      (node (ref "S5") (pin "P$3") (pinfunction "S_P$3") (pintype "passive"))
    )
    (net (code "101") (name "Net-(S5-P1)") (class "Default")
      (node (ref "S5") (pin "P$2") (pinfunction "P1_P$2") (pintype "passive"))
      (node (ref "S8") (pin "P$1") (pinfunction "P_P$1") (pintype "passive"))
    )
    (net (code "102") (name "Net-(S5-S1)") (class "Default")
      (node (ref "S5") (pin "P$4") (pinfunction "S1_P$4") (pintype "passive"))
      (node (ref "S6") (pin "P$3") (pinfunction "S_P$3") (pintype "passive"))
    )
    (net (code "103") (name "Net-(S6-P1)") (class "Default")
      (node (ref "S6") (pin "P$2") (pinfunction "P1_P$2") (pintype "passive"))
      (node (ref "S9") (pin "P$1") (pinfunction "P_P$1") (pintype "passive"))
    )
    (net (code "104") (name "Net-(S7-S1)") (class "Default")
      (node (ref "S7") (pin "P$4") (pinfunction "S1_P$4") (pintype "passive"))
      (node (ref "S8") (pin "P$3") (pinfunction "S_P$3") (pintype "passive"))
    )
    (net (code "105") (name "Net-(S8-S1)") (class "Default")
      (node (ref "S8") (pin "P$4") (pinfunction "S1_P$4") (pintype "passive"))
      (node (ref "S9") (pin "P$3") (pinfunction "S_P$3") (pintype "passive"))
    )
    (net (code "106") (name "Net-(SDOWN-P)") (class "Default")
      (node (ref "SDOWN") (pin "P$1") (pinfunction "P_P$1") (pintype "passive"))
      (node (ref "SUP") (pin "P$2") (pinfunction "P1_P$2") (pintype "passive"))
    )
    (net (code "107") (name "Net-(SDOWN-S)") (class "Default")
      (node (ref "SDOWN") (pin "P$3") (pinfunction "S_P$3") (pintype "passive"))
      (node (ref "SLEFT") (pin "P$4") (pinfunction "S1_P$4") (pintype "passive"))
    )
    (net (code "108") (name "Net-(SDOWN-S1)") (class "Default")
      (node (ref "SDOWN") (pin "P$4") (pinfunction "S1_P$4") (pintype "passive"))
      (node (ref "SRIGHT") (pin "P$3") (pinfunction "S_P$3") (pintype "passive"))
    )
    (net (code "109") (name "Net-(U$3-2)") (class "Default")
      (node (ref "D1") (pin "A") (pinfunction "A_A") (pintype "passive"))
      (node (ref "T1") (pin "C") (pinfunction "C_C") (pintype "passive"))
      (node (ref "U$3") (pin "-") (pinfunction "2_-") (pintype "passive"))
    )
    (net (code "110") (name "Net-(U1-PROG)") (class "Default")
      (node (ref "R7") (pin "1") (pinfunction "1_1") (pintype "passive"))
      (node (ref "U1") (pin "5") (pinfunction "PROG_5") (pintype "input"))
    )
    (net (code "111") (name "Net-(U1-STAT)") (class "Default")
      (node (ref "R9") (pin "1") (pinfunction "1_1") (pintype "passive"))
      (node (ref "U1") (pin "1") (pinfunction "STAT_1") (pintype "output"))
    )
    (net (code "112") (name "SIM_CLK") (class "Default")
      (node (ref "R2") (pin "1") (pinfunction "1_1") (pintype "passive"))
      (node (ref "U7") (pin "P$14") (pinfunction "14-SIM_CLK_P$14") (pintype "bidirectional"))
    )
    (net (code "113") (name "SIM_DATA") (class "Default")
      (node (ref "R3") (pin "1") (pinfunction "1_1") (pintype "passive"))
      (node (ref "U7") (pin "P$13") (pinfunction "13-SIM_DATA_P$13") (pintype "bidirectional"))
    )
    (net (code "114") (name "SIM_RST") (class "Default")
      (node (ref "R1") (pin "1") (pinfunction "1_1") (pintype "passive"))
      (node (ref "U7") (pin "P$15") (pinfunction "15-SIM_RST_P$15") (pintype "bidirectional"))
    )
    (net (code "115") (name "SIM_VDD") (class "Default")
      (node (ref "U7") (pin "P$12") (pinfunction "12-SIM_VDD_P$12") (pintype "bidirectional"))
      (node (ref "X3") (pin "C1") (pinfunction "1_C1") (pintype "passive"))
    )
    (net (code "116") (name "unconnected-(IC1-(TCK{slash}PCINT18)PC2-Pad21)") (class "Default")
      (node (ref "IC1") (pin "21") (pinfunction "(TCK/PCINT18)PC2_21") (pintype "bidirectional"))
    )
    (net (code "117") (name "unconnected-(IC1-(TDI{slash}PCINT21)PC5-Pad24)") (class "Default")
      (node (ref "IC1") (pin "24") (pinfunction "(TDI/PCINT21)PC5_24") (pintype "bidirectional"))
    )
    (net (code "118") (name "unconnected-(IC1-(TDO{slash}PCINT20)PC4-Pad23)") (class "Default")
      (node (ref "IC1") (pin "23") (pinfunction "(TDO/PCINT20)PC4_23") (pintype "bidirectional"))
    )
    (net (code "119") (name "unconnected-(IC1-(TOSC1{slash}PCINT22)PC6-Pad25)") (class "Default")
      (node (ref "IC1") (pin "25") (pinfunction "(TOSC1/PCINT22)PC6_25") (pintype "bidirectional"))
    )
    (net (code "120") (name "unconnected-(JP4-Pad2)") (class "Default")
      (node (ref "JP4") (pin "2") (pinfunction "2_2") (pintype "passive"))
    )
    (net (code "121") (name "unconnected-(S#-P1-PadP$2)") (class "Default")
      (node (ref "S#") (pin "P$2") (pinfunction "P1_P$2") (pintype "passive"))
    )
    (net (code "122") (name "unconnected-(S#-S1-PadP$4)") (class "Default")
      (node (ref "S#") (pin "P$4") (pinfunction "S1_P$4") (pintype "passive"))
    )
    (net (code "123") (name "unconnected-(S*-P1-PadP$2)") (class "Default")
      (node (ref "S*") (pin "P$2") (pinfunction "P1_P$2") (pintype "passive"))
    )
    (net (code "124") (name "unconnected-(S0-P1-PadP$2)") (class "Default")
      (node (ref "S0") (pin "P$2") (pinfunction "P1_P$2") (pintype "passive"))
    )
    (net (code "125") (name "unconnected-(S3-S1-PadP$4)") (class "Default")
      (node (ref "S3") (pin "P$4") (pinfunction "S1_P$4") (pintype "passive"))
    )
    (net (code "126") (name "unconnected-(S6-S1-PadP$4)") (class "Default")
      (node (ref "S6") (pin "P$4") (pinfunction "S1_P$4") (pintype "passive"))
    )
    (net (code "127") (name "unconnected-(S9-S1-PadP$4)") (class "Default")
      (node (ref "S9") (pin "P$4") (pinfunction "S1_P$4") (pintype "passive"))
    )
    (net (code "128") (name "unconnected-(SRIGHT-S1-PadP$4)") (class "Default")
      (node (ref "SRIGHT") (pin "P$4") (pinfunction "S1_P$4") (pintype "passive"))
    )
    (net (code "129") (name "unconnected-(SUP-S1-PadP$4)") (class "Default")
      (node (ref "SUP") (pin "P$4") (pinfunction "S1_P$4") (pintype "passive"))
    )
    (net (code "130") (name "unconnected-(U$1-MTN1-PadMTN3)") (class "Default")
      (node (ref "U$1") (pin "MTN3") (pinfunction "MTN1_MTN3") (pintype "bidirectional"))
    )
    (net (code "131") (name "unconnected-(U$1-MTN2-PadMTN1)") (class "Default")
      (node (ref "U$1") (pin "MTN1") (pinfunction "MTN2_MTN1") (pintype "bidirectional"))
    )
    (net (code "132") (name "unconnected-(U$1-MTN3-PadMTN2)") (class "Default")
      (node (ref "U$1") (pin "MTN2") (pinfunction "MTN3_MTN2") (pintype "bidirectional"))
    )
    (net (code "133") (name "unconnected-(U$1-PadD+)") (class "Default")
      (node (ref "U$1") (pin "D+") (pinfunction "D+_D+") (pintype "bidirectional"))
    )
    (net (code "134") (name "unconnected-(U$1-PadD-)") (class "Default")
      (node (ref "U$1") (pin "D-") (pinfunction "D-_D-") (pintype "bidirectional"))
    )
    (net (code "135") (name "unconnected-(U$1-PadID)") (class "Default")
      (node (ref "U$1") (pin "ID") (pinfunction "ID_ID") (pintype "bidirectional"))
    )
    (net (code "136") (name "unconnected-(U$1-PadMTN4)") (class "Default")
      (node (ref "U$1") (pin "MTN4") (pinfunction "MTN4_MTN4") (pintype "bidirectional"))
    )
    (net (code "137") (name "unconnected-(U$2-DN'-PadP$14)") (class "Default")
      (node (ref "U$2") (pin "P$14") (pinfunction "DN'_P$14") (pintype "bidirectional"))
    )
    (net (code "138") (name "unconnected-(U$2-D{slash}C'-PadP$13)") (class "Default")
      (node (ref "U$2") (pin "P$13") (pinfunction "D/C'_P$13") (pintype "bidirectional"))
    )
    (net (code "139") (name "unconnected-(U$2-GND'-PadP$10)") (class "Default")
      (node (ref "U$2") (pin "P$10") (pinfunction "GND'_P$10") (pintype "bidirectional"))
    )
    (net (code "140") (name "unconnected-(U$2-LED'-PadP$16)") (class "Default")
      (node (ref "U$2") (pin "P$16") (pinfunction "LED'_P$16") (pintype "bidirectional"))
    )
    (net (code "141") (name "unconnected-(U$2-RST'-PadP$12)") (class "Default")
      (node (ref "U$2") (pin "P$12") (pinfunction "RST'_P$12") (pintype "bidirectional"))
    )
    (net (code "142") (name "unconnected-(U$2-SCE'-PadP$11)") (class "Default")
      (node (ref "U$2") (pin "P$11") (pinfunction "SCE'_P$11") (pintype "bidirectional"))
    )
    (net (code "143") (name "unconnected-(U$2-SCLK'-PadP$15)") (class "Default")
      (node (ref "U$2") (pin "P$15") (pinfunction "SCLK'_P$15") (pintype "bidirectional"))
    )
    (net (code "144") (name "unconnected-(U$2-VCC'-PadP$9)") (class "Default")
      (node (ref "U$2") (pin "P$9") (pinfunction "VCC'_P$9") (pintype "bidirectional"))
    )
    (net (code "145") (name "unconnected-(U7-7-VDD_EXT-PadP$7)") (class "Default")
      (node (ref "U7") (pin "P$7") (pinfunction "7-VDD_EXT_P$7") (pintype "bidirectional"))
    )
    (net (code "146") (name "unconnected-(U7-11-SIM_PRESENCE-PadP$11)") (class "Default")
      (node (ref "U7") (pin "P$11") (pinfunction "11-SIM_PRESENCE_P$11") (pintype "bidirectional"))
    )
    (net (code "147") (name "unconnected-(U7-17-EMERG_OFF-PadP$17)") (class "Default")
      (node (ref "U7") (pin "P$17") (pinfunction "17-EMERG_OFF_P$17") (pintype "bidirectional"))
    )
    (net (code "148") (name "unconnected-(U7-40-TEMP_BAT-PadP$40)") (class "Default")
      (node (ref "U7") (pin "P$40") (pinfunction "40-TEMP_BAT_P$40") (pintype "bidirectional"))
    )
    (net (code "149") (name "unconnected-(U7-53-VCHG-PadP$53)") (class "Default")
      (node (ref "U7") (pin "P$53") (pinfunction "53-VCHG_P$53") (pintype "bidirectional"))
    )
    (net (code "150") (name "unconnected-(U7-56-DCD-PadP$56)") (class "Default")
      (node (ref "U7") (pin "P$56") (pinfunction "56-DCD_P$56") (pintype "bidirectional"))
    )
    (net (code "151") (name "unconnected-(U7-57-CTS-PadP$57)") (class "Default")
      (node (ref "U7") (pin "P$57") (pinfunction "57-CTS_P$57") (pintype "bidirectional"))
    )
    (net (code "152") (name "unconnected-(U7-58-RTS-PadP$58)") (class "Default")
      (node (ref "U7") (pin "P$58") (pinfunction "58-RTS_P$58") (pintype "bidirectional"))
    )
    (net (code "153") (name "unconnected-(U7-62-TXD3-PadP$62)") (class "Default")
      (node (ref "U7") (pin "P$62") (pinfunction "62-TXD3_P$62") (pintype "bidirectional"))
    )
    (net (code "154") (name "unconnected-(U7-63-RXD3-PadP$63)") (class "Default")
      (node (ref "U7") (pin "P$63") (pinfunction "63-RXD3_P$63") (pintype "bidirectional"))
    )
    (net (code "155") (name "unconnected-(X3-5-PadC6)") (class "Default")
      (node (ref "X3") (pin "C6") (pinfunction "5_C6") (pintype "passive"))
    )
  )
)
